# design.net
KiCad netlist of a schematic drawn in EasyEDA Pro
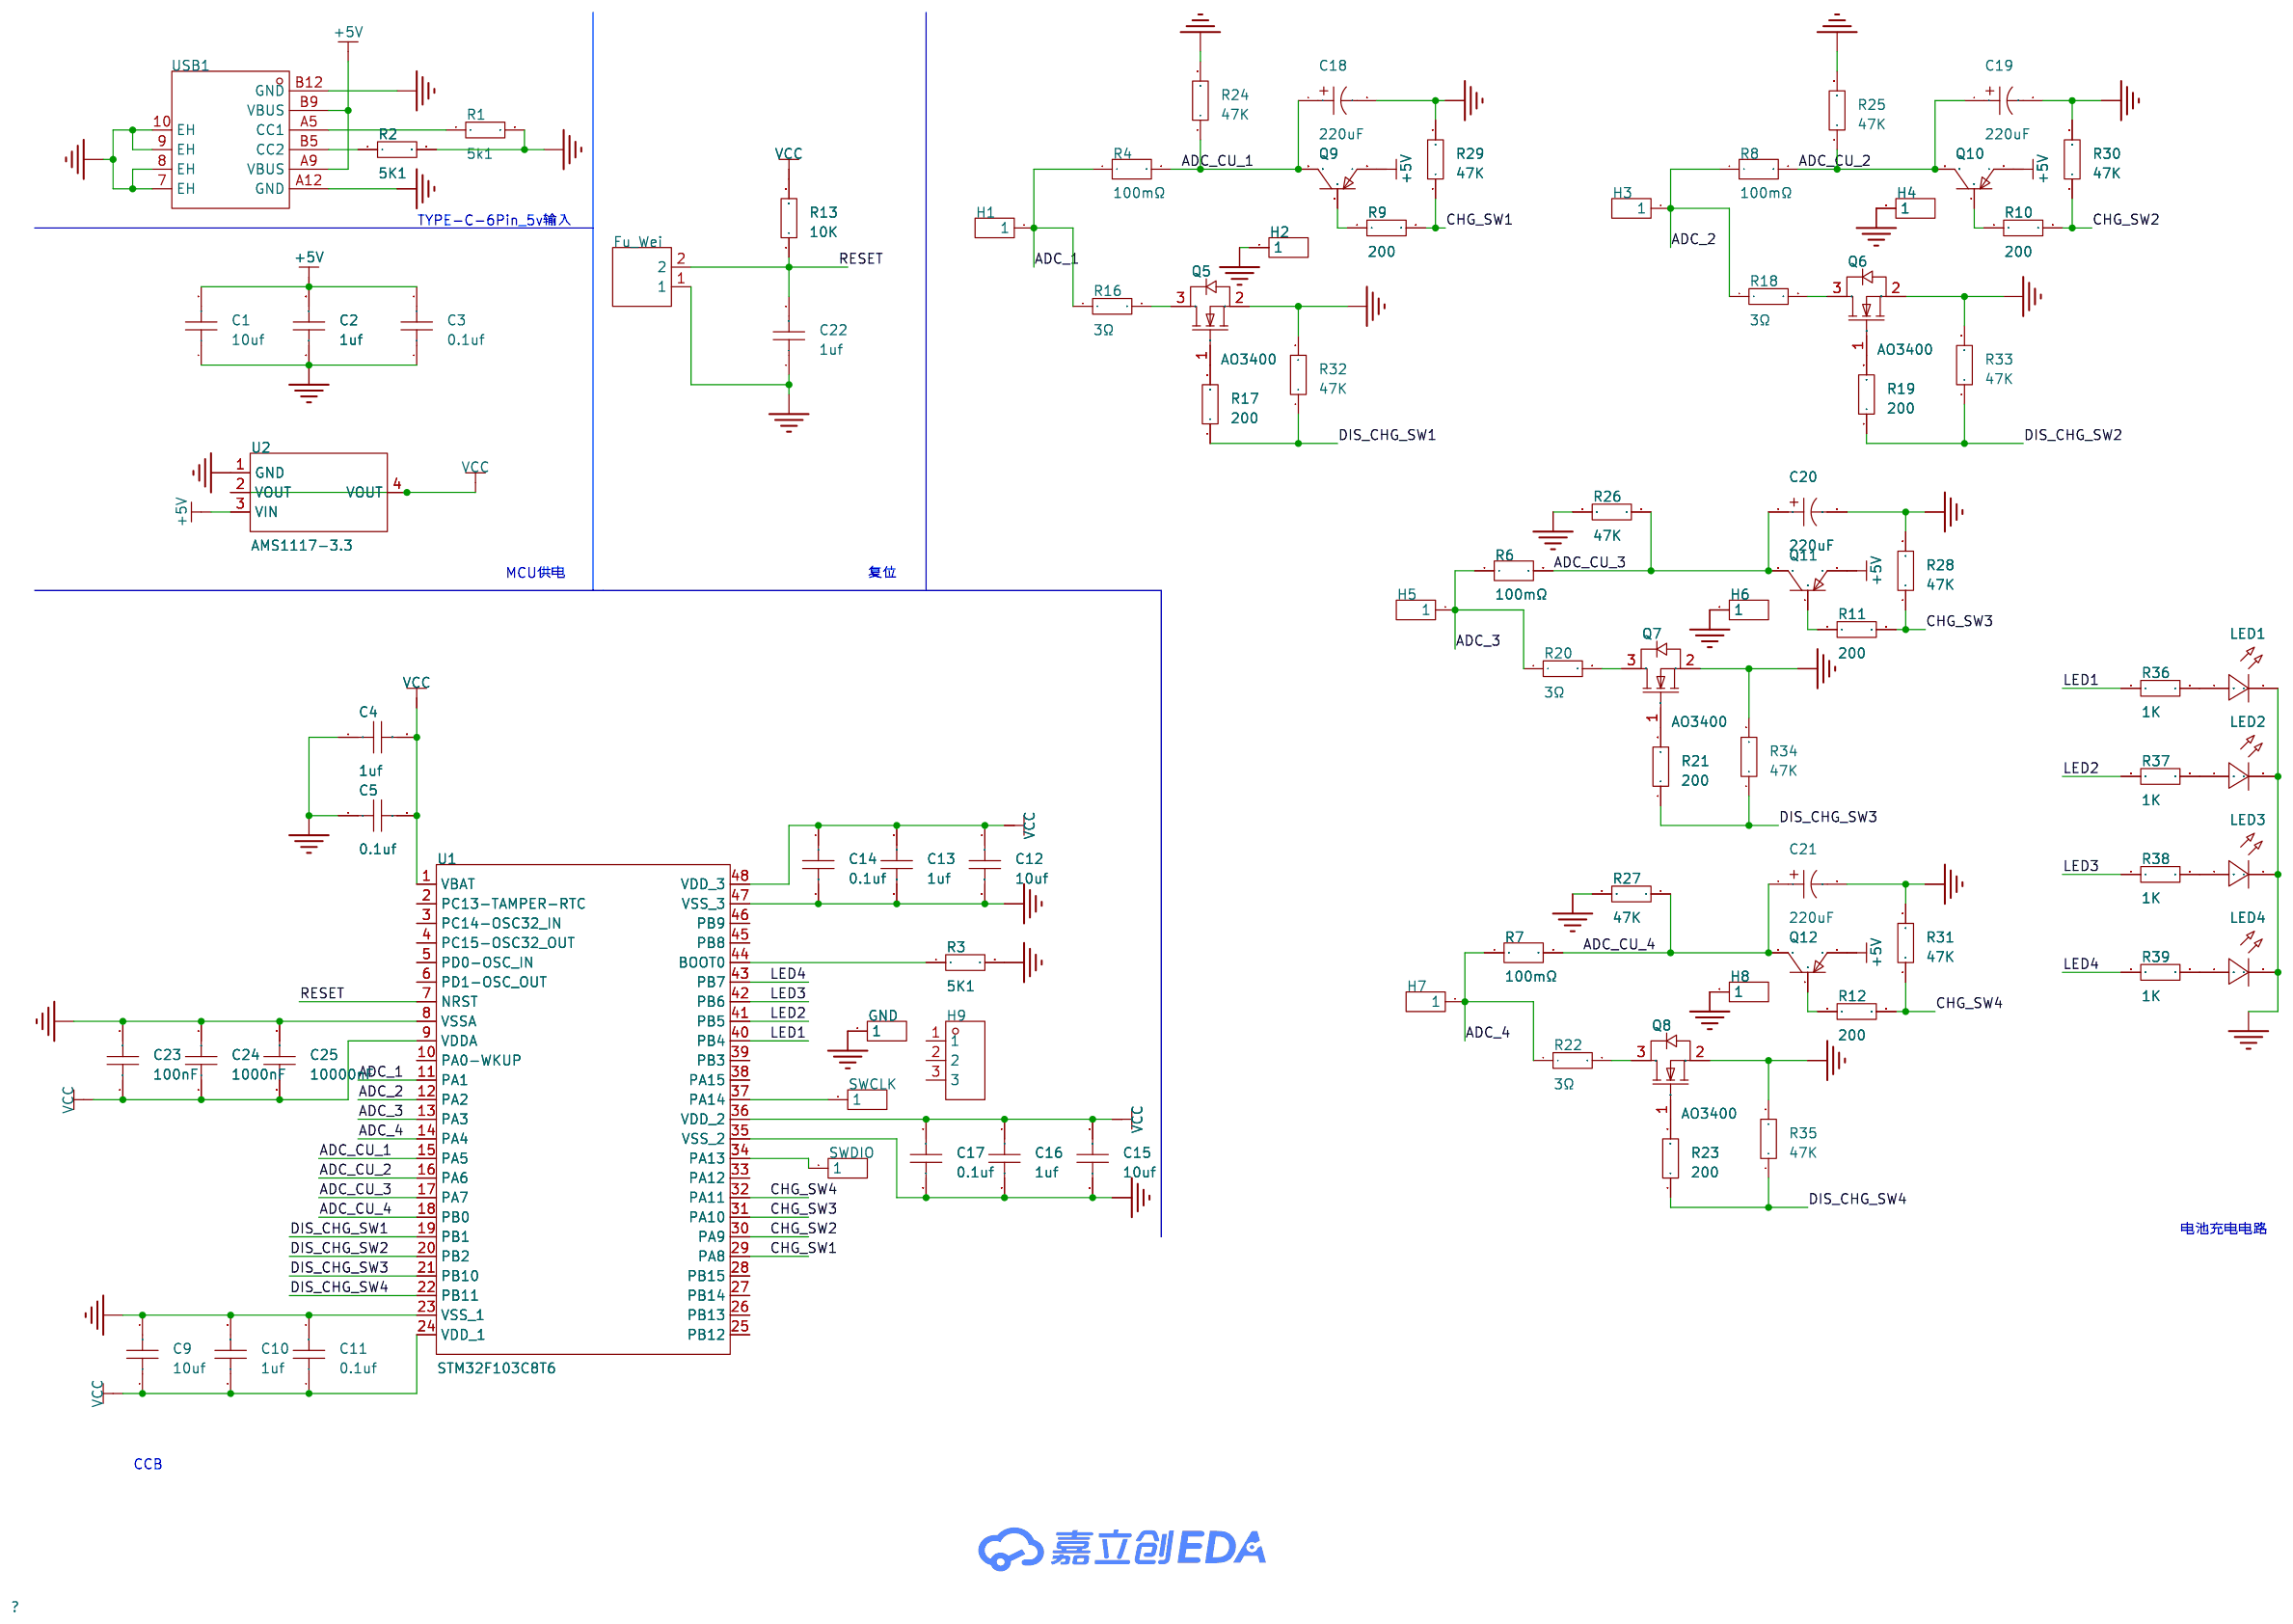
[diagram p0: schematic sheet]

(export (version "E")
  (design (tool "Eeschema 10.0.6"))
  (components
    (comp (ref "C1")
      (value "10uf")
      (footprint "easyedapro:C0603")
      (libsource (lib "easyedapro") (part "Capacitance"))
    )
    (comp (ref "C2")
      (value "1uf")
      (footprint "easyedapro:C0603")
      (libsource (lib "easyedapro") (part "Capacitance"))
    )
    (comp (ref "C3")
      (value "0.1uf")
      (footprint "easyedapro:C0603")
      (libsource (lib "easyedapro") (part "Capacitance"))
    )
    (comp (ref "C4")
      (value "1uf")
      (footprint "easyedapro:C0603")
      (libsource (lib "easyedapro") (part "Capacitance"))
    )
    (comp (ref "C5")
      (value "0.1uf")
      (footprint "easyedapro:C0603")
      (libsource (lib "easyedapro") (part "Capacitance"))
    )
    (comp (ref "C9")
      (value "10uf")
      (footprint "easyedapro:C0603")
      (libsource (lib "easyedapro") (part "Capacitance"))
    )
    (comp (ref "C10")
      (value "1uf")
      (footprint "easyedapro:C0603")
      (libsource (lib "easyedapro") (part "Capacitance"))
    )
    (comp (ref "C11")
      (value "0.1uf")
      (footprint "easyedapro:C0603")
      (libsource (lib "easyedapro") (part "Capacitance"))
    )
    (comp (ref "C12")
      (value "10uf")
      (footprint "easyedapro:C0603")
      (libsource (lib "easyedapro") (part "Capacitance"))
    )
    (comp (ref "C13")
      (value "1uf")
      (footprint "easyedapro:C0603")
      (libsource (lib "easyedapro") (part "Capacitance"))
    )
    (comp (ref "C14")
      (value "0.1uf")
      (footprint "easyedapro:C0603")
      (libsource (lib "easyedapro") (part "Capacitance"))
    )
    (comp (ref "C15")
      (value "10uf")
      (footprint "easyedapro:C0603")
      (libsource (lib "easyedapro") (part "Capacitance"))
    )
    (comp (ref "C16")
      (value "1uf")
      (footprint "easyedapro:C0603")
      (libsource (lib "easyedapro") (part "Capacitance"))
    )
    (comp (ref "C17")
      (value "0.1uf")
      (footprint "easyedapro:C0603")
      (libsource (lib "easyedapro") (part "Capacitance"))
    )
    (comp (ref "C18")
      (value "220uF")
      (footprint "easyedapro:CAP-SMD_L6.0-W3.2")
      (description "容值:220uF;精度:±20%;额定电压:6.3V;等效串联电阻(ESR):45mΩ@100kHz;")
      (fields
        (field (name "Manufacturer Part") "T520C227M006ATE045")
        (field (name "Manufacturer") "KEMET(基美)")
      )
      (libsource (lib "easyedapro") (part "T520C227M006ATE045"))
    )
    (comp (ref "C19")
      (value "220uF")
      (footprint "easyedapro:CAP-SMD_L6.0-W3.2")
      (description "容值:220uF;精度:±20%;额定电压:6.3V;等效串联电阻(ESR):45mΩ@100kHz;")
      (fields
        (field (name "Manufacturer Part") "T520C227M006ATE045")
        (field (name "Manufacturer") "KEMET(基美)")
      )
      (libsource (lib "easyedapro") (part "T520C227M006ATE045"))
    )
    (comp (ref "C20")
      (value "220uF")
      (footprint "easyedapro:CAP-SMD_L6.0-W3.2")
      (description "容值:220uF;精度:±20%;额定电压:6.3V;等效串联电阻(ESR):45mΩ@100kHz;")
      (fields
        (field (name "Manufacturer Part") "T520C227M006ATE045")
        (field (name "Manufacturer") "KEMET(基美)")
      )
      (libsource (lib "easyedapro") (part "T520C227M006ATE045"))
    )
    (comp (ref "C21")
      (value "220uF")
      (footprint "easyedapro:CAP-SMD_L6.0-W3.2")
      (description "容值:220uF;精度:±20%;额定电压:6.3V;等效串联电阻(ESR):45mΩ@100kHz;")
      (fields
        (field (name "Manufacturer Part") "T520C227M006ATE045")
        (field (name "Manufacturer") "KEMET(基美)")
      )
      (libsource (lib "easyedapro") (part "T520C227M006ATE045"))
    )
    (comp (ref "C22")
      (value "1uf")
      (footprint "easyedapro:C0603")
      (libsource (lib "easyedapro") (part "Capacitance"))
    )
    (comp (ref "C23")
      (value "100nF")
      (footprint "easyedapro:C0603")
      (libsource (lib "easyedapro") (part "Capacitance"))
    )
    (comp (ref "C24")
      (value "1000nF")
      (footprint "easyedapro:C0603")
      (libsource (lib "easyedapro") (part "Capacitance"))
    )
    (comp (ref "C25")
      (value "10000nF")
      (footprint "easyedapro:C0603")
      (libsource (lib "easyedapro") (part "Capacitance"))
    )
    (comp (ref "Fu_Wei")
      (value "~")
      (footprint "easyedapro:HDR-TH_2P-P2.54-V-M-1")
      (libsource (lib "easyedapro") (part "210S-1*2P L=11.6MMGold-plated black"))
    )
    (comp (ref "GND")
      (value "~")
      (footprint "easyedapro:HDR-TH_1P-V-M_XKB_X4611WV-01I-C28D40")
      (libsource (lib "easyedapro") (part "HDR_1x1"))
    )
    (comp (ref "H1")
      (value "~")
      (footprint "easyedapro:HDR-TH_1P-V-M_XKB_X4611WV-01I-C28D40")
      (libsource (lib "easyedapro") (part "HDR_1x1"))
    )
    (comp (ref "H2")
      (value "~")
      (footprint "easyedapro:HDR-TH_1P-V-M_XKB_X4611WV-01I-C28D40")
      (libsource (lib "easyedapro") (part "HDR_1x1"))
    )
    (comp (ref "H3")
      (value "~")
      (footprint "easyedapro:HDR-TH_1P-V-M_XKB_X4611WV-01I-C28D40")
      (libsource (lib "easyedapro") (part "HDR_1x1"))
    )
    (comp (ref "H4")
      (value "~")
      (footprint "easyedapro:HDR-TH_1P-V-M_XKB_X4611WV-01I-C28D40")
      (libsource (lib "easyedapro") (part "HDR_1x1"))
    )
    (comp (ref "H5")
      (value "~")
      (footprint "easyedapro:HDR-TH_1P-V-M_XKB_X4611WV-01I-C28D40")
      (libsource (lib "easyedapro") (part "HDR_1x1"))
    )
    (comp (ref "H6")
      (value "~")
      (footprint "easyedapro:HDR-TH_1P-V-M_XKB_X4611WV-01I-C28D40")
      (libsource (lib "easyedapro") (part "HDR_1x1"))
    )
    (comp (ref "H7")
      (value "~")
      (footprint "easyedapro:HDR-TH_1P-V-M_XKB_X4611WV-01I-C28D40")
      (libsource (lib "easyedapro") (part "HDR_1x1"))
    )
    (comp (ref "H8")
      (value "~")
      (footprint "easyedapro:HDR-TH_1P-V-M_XKB_X4611WV-01I-C28D40")
      (libsource (lib "easyedapro") (part "HDR_1x1"))
    )
    (comp (ref "H9")
      (value "~")
      (footprint "easyedapro:HDR-TH_3P-P2.54-V-M")
      (libsource (lib "easyedapro") (part "HDR-M_2.54_1x3P"))
    )
    (comp (ref "LED1")
      (value "~")
      (footprint "easyedapro:LED_TH-3mm")
      (libsource (lib "easyedapro") (part "LED_TH-R"))
    )
    (comp (ref "LED2")
      (value "~")
      (footprint "easyedapro:LED_TH-3mm")
      (libsource (lib "easyedapro") (part "LED_TH-R"))
    )
    (comp (ref "LED3")
      (value "~")
      (footprint "easyedapro:LED_TH-3mm")
      (libsource (lib "easyedapro") (part "LED_TH-R"))
    )
    (comp (ref "LED4")
      (value "~")
      (footprint "easyedapro:LED_TH-3mm")
      (libsource (lib "easyedapro") (part "LED_TH-R"))
    )
    (comp (ref "Q5")
      (value "AO3400")
      (footprint "easyedapro:SOT-23_L2.9-W1.3-P1.90-LS2.4-BR")
      (fields (field (name "Manufacturer") "GOODWORK(固得沃克)"))
      (libsource (lib "easyedapro") (part "AO3400_C2938367"))
    )
    (comp (ref "Q6")
      (value "AO3400")
      (footprint "easyedapro:SOT-23_L2.9-W1.3-P1.90-LS2.4-BR")
      (fields (field (name "Manufacturer") "GOODWORK(固得沃克)"))
      (libsource (lib "easyedapro") (part "AO3400_C2938367"))
    )
    (comp (ref "Q7")
      (value "AO3400")
      (footprint "easyedapro:SOT-23_L2.9-W1.3-P1.90-LS2.4-BR")
      (fields (field (name "Manufacturer") "GOODWORK(固得沃克)"))
      (libsource (lib "easyedapro") (part "AO3400_C2938367"))
    )
    (comp (ref "Q8")
      (value "AO3400")
      (footprint "easyedapro:SOT-23_L2.9-W1.3-P1.90-LS2.4-BR")
      (fields (field (name "Manufacturer") "GOODWORK(固得沃克)"))
      (libsource (lib "easyedapro") (part "AO3400_C2938367"))
    )
    (comp (ref "Q9")
      (value "~")
      (footprint "easyedapro:S8550P_SOT")
      (libsource (lib "easyedapro") (part "PNP"))
    )
    (comp (ref "Q10")
      (value "~")
      (footprint "easyedapro:S8550P_SOT")
      (libsource (lib "easyedapro") (part "PNP"))
    )
    (comp (ref "Q11")
      (value "~")
      (footprint "easyedapro:S8550P_SOT")
      (libsource (lib "easyedapro") (part "PNP"))
    )
    (comp (ref "Q12")
      (value "~")
      (footprint "easyedapro:S8550P_SOT")
      (libsource (lib "easyedapro") (part "PNP"))
    )
    (comp (ref "R1") (value "5k1") (footprint "easyedapro:R0805") (libsource (lib "easyedapro") (part "电阻")))
    (comp (ref "R2") (value "5K1") (footprint "easyedapro:R0805") (libsource (lib "easyedapro") (part "电阻")))
    (comp (ref "R3") (value "5K1") (footprint "easyedapro:R0805") (libsource (lib "easyedapro") (part "电阻")))
    (comp (ref "R4")
      (value "100mΩ")
      (footprint "easyedapro:R2512")
      (description "电阻类型:采样电阻；合金电阻;阻值:100mΩ;精度:±1%;功率:3W;温度系数:±50ppm/°C;")
      (fields (field (name "Manufacturer Part") "RE2512F3R100") (field (name "Manufacturer") "JIERR(捷而瑞)"))
      (libsource (lib "easyedapro") (part "RE2512F3R100"))
    )
    (comp (ref "R6")
      (value "100mΩ")
      (footprint "easyedapro:R2512")
      (description "电阻类型:采样电阻；合金电阻;阻值:100mΩ;精度:±1%;功率:3W;温度系数:±50ppm/°C;")
      (fields (field (name "Manufacturer Part") "RE2512F3R100") (field (name "Manufacturer") "JIERR(捷而瑞)"))
      (libsource (lib "easyedapro") (part "RE2512F3R100"))
    )
    (comp (ref "R7")
      (value "100mΩ")
      (footprint "easyedapro:R2512")
      (description "电阻类型:采样电阻；合金电阻;阻值:100mΩ;精度:±1%;功率:3W;温度系数:±50ppm/°C;")
      (fields (field (name "Manufacturer Part") "RE2512F3R100") (field (name "Manufacturer") "JIERR(捷而瑞)"))
      (libsource (lib "easyedapro") (part "RE2512F3R100"))
    )
    (comp (ref "R8")
      (value "100mΩ")
      (footprint "easyedapro:R2512")
      (description "电阻类型:采样电阻；合金电阻;阻值:100mΩ;精度:±1%;功率:3W;温度系数:±50ppm/°C;")
      (fields (field (name "Manufacturer Part") "RE2512F3R100") (field (name "Manufacturer") "JIERR(捷而瑞)"))
      (libsource (lib "easyedapro") (part "RE2512F3R100"))
    )
    (comp (ref "R9") (value "200") (footprint "easyedapro:R0805") (libsource (lib "easyedapro") (part "电阻")))
    (comp (ref "R10") (value "200") (footprint "easyedapro:R0805") (libsource (lib "easyedapro") (part "电阻")))
    (comp (ref "R11") (value "200") (footprint "easyedapro:R0805") (libsource (lib "easyedapro") (part "电阻")))
    (comp (ref "R12") (value "200") (footprint "easyedapro:R0805") (libsource (lib "easyedapro") (part "电阻")))
    (comp (ref "R13") (value "10K") (footprint "easyedapro:R0805") (libsource (lib "easyedapro") (part "电阻")))
    (comp (ref "R16")
      (value "3Ω")
      (footprint "easyedapro:R2512")
      (description "电阻类型:厚膜电阻;阻值:3Ω;精度:±5%;功率:1W;最大工作电压:200V;温度系数:±200ppm/°C;")
      (fields
        (field (name "Manufacturer Part") "25121WJ030JT4E")
        (field (name "Manufacturer") "UNI-ROYAL(厚声)")
      )
      (libsource (lib "easyedapro") (part "25121WJ030JT4E"))
    )
    (comp (ref "R17") (value "200") (footprint "easyedapro:R0805") (libsource (lib "easyedapro") (part "电阻")))
    (comp (ref "R18")
      (value "3Ω")
      (footprint "easyedapro:R2512")
      (description "电阻类型:厚膜电阻;阻值:3Ω;精度:±5%;功率:1W;最大工作电压:200V;温度系数:±200ppm/°C;")
      (fields
        (field (name "Manufacturer Part") "25121WJ030JT4E")
        (field (name "Manufacturer") "UNI-ROYAL(厚声)")
      )
      (libsource (lib "easyedapro") (part "25121WJ030JT4E"))
    )
    (comp (ref "R19") (value "200") (footprint "easyedapro:R0805") (libsource (lib "easyedapro") (part "电阻")))
    (comp (ref "R20")
      (value "3Ω")
      (footprint "easyedapro:R2512")
      (description "电阻类型:厚膜电阻;阻值:3Ω;精度:±5%;功率:1W;最大工作电压:200V;温度系数:±200ppm/°C;")
      (fields
        (field (name "Manufacturer Part") "25121WJ030JT4E")
        (field (name "Manufacturer") "UNI-ROYAL(厚声)")
      )
      (libsource (lib "easyedapro") (part "25121WJ030JT4E"))
    )
    (comp (ref "R21") (value "200") (footprint "easyedapro:R0805") (libsource (lib "easyedapro") (part "电阻")))
    (comp (ref "R22")
      (value "3Ω")
      (footprint "easyedapro:R2512")
      (description "电阻类型:厚膜电阻;阻值:3Ω;精度:±5%;功率:1W;最大工作电压:200V;温度系数:±200ppm/°C;")
      (fields
        (field (name "Manufacturer Part") "25121WJ030JT4E")
        (field (name "Manufacturer") "UNI-ROYAL(厚声)")
      )
      (libsource (lib "easyedapro") (part "25121WJ030JT4E"))
    )
    (comp (ref "R23") (value "200") (footprint "easyedapro:R0805") (libsource (lib "easyedapro") (part "电阻")))
    (comp (ref "R24") (value "47K") (footprint "easyedapro:R0805") (libsource (lib "easyedapro") (part "电阻")))
    (comp (ref "R25") (value "47K") (footprint "easyedapro:R0805") (libsource (lib "easyedapro") (part "电阻")))
    (comp (ref "R26") (value "47K") (footprint "easyedapro:R0805") (libsource (lib "easyedapro") (part "电阻")))
    (comp (ref "R27") (value "47K") (footprint "easyedapro:R0805") (libsource (lib "easyedapro") (part "电阻")))
    (comp (ref "R28") (value "47K") (footprint "easyedapro:R0805") (libsource (lib "easyedapro") (part "电阻")))
    (comp (ref "R29") (value "47K") (footprint "easyedapro:R0805") (libsource (lib "easyedapro") (part "电阻")))
    (comp (ref "R30") (value "47K") (footprint "easyedapro:R0805") (libsource (lib "easyedapro") (part "电阻")))
    (comp (ref "R31") (value "47K") (footprint "easyedapro:R0805") (libsource (lib "easyedapro") (part "电阻")))
    (comp (ref "R32") (value "47K") (footprint "easyedapro:R0805") (libsource (lib "easyedapro") (part "电阻")))
    (comp (ref "R33") (value "47K") (footprint "easyedapro:R0805") (libsource (lib "easyedapro") (part "电阻")))
    (comp (ref "R34") (value "47K") (footprint "easyedapro:R0805") (libsource (lib "easyedapro") (part "电阻")))
    (comp (ref "R35") (value "47K") (footprint "easyedapro:R0805") (libsource (lib "easyedapro") (part "电阻")))
    (comp (ref "R36") (value "1K") (footprint "easyedapro:R0805") (libsource (lib "easyedapro") (part "电阻")))
    (comp (ref "R37") (value "1K") (footprint "easyedapro:R0805") (libsource (lib "easyedapro") (part "电阻")))
    (comp (ref "R38") (value "1K") (footprint "easyedapro:R0805") (libsource (lib "easyedapro") (part "电阻")))
    (comp (ref "R39") (value "1K") (footprint "easyedapro:R0805") (libsource (lib "easyedapro") (part "电阻")))
    (comp (ref "SWCLK")
      (value "~")
      (footprint "easyedapro:HDR-TH_1P-V-M_XKB_X4611WV-01I-C28D40")
      (libsource (lib "easyedapro") (part "HDR_1x1"))
    )
    (comp (ref "SWDIO")
      (value "~")
      (footprint "easyedapro:HDR-TH_1P-V-M_XKB_X4611WV-01I-C28D40")
      (libsource (lib "easyedapro") (part "HDR_1x1"))
    )
    (comp (ref "U1")
      (value "STM32F103C8T6")
      (footprint "easyedapro:LQFP-48_L7.0-W7.0-P0.50-LS9.0-BL")
      (description "CPU内核:ARM-M3;CPU最大主频:72MHz;应用领域:-;")
      (fields (field (name "Manufacturer") "ST(意法半导体)"))
      (libsource (lib "easyedapro") (part "STM32F103C8T6"))
    )
    (comp (ref "U2")
      (value "AMS1117-3.3")
      (footprint "easyedapro:SOT-223-3_L6.5-W3.4-P2.30-LS7.0-BR")
      (description "输出类型:固定;工作电压:16V;输出电压:3.3V;输出电流:1A;电源纹波抑制比(PSRR):72dB@(120Hz);输出极性:正极;")
      (fields (field (name "Manufacturer") "AMS"))
      (libsource (lib "easyedapro") (part "AMS1117-3.3"))
    )
    (comp (ref "USB1")
      (value "~")
      (footprint "easyedapro:USB_ TYPE-C-6P")
      (libsource (lib "easyedapro") (part "USB_ TYPE-C-6P"))
    )
  )
  (nets
    (net (code "1") (name "+5V") (class "Default")
      (node (ref "C1") (pin "2") (pinfunction "2_2") (pintype "input"))
      (node (ref "C2") (pin "2") (pinfunction "2_2") (pintype "input"))
      (node (ref "C3") (pin "2") (pinfunction "2_2") (pintype "input"))
      (node (ref "Q10") (pin "2") (pinfunction "E_2") (pintype "input"))
      (node (ref "Q11") (pin "2") (pinfunction "E_2") (pintype "input"))
      (node (ref "Q12") (pin "2") (pinfunction "E_2") (pintype "input"))
      (node (ref "Q9") (pin "2") (pinfunction "E_2") (pintype "input"))
      (node (ref "U2") (pin "3") (pinfunction "VIN_3") (pintype "unspecified"))
      (node (ref "USB1") (pin "A9") (pinfunction "VBUS_A9") (pintype "input"))
      (node (ref "USB1") (pin "B9") (pinfunction "VBUS_B9") (pintype "input"))
    )
    (net (code "2") (name "/ADC_1") (class "Default")
      (node (ref "H1") (pin "1") (pinfunction "1_1") (pintype "unspecified"))
      (node (ref "R16") (pin "1") (pinfunction "1_1") (pintype "input"))
      (node (ref "R4") (pin "1") (pinfunction "1_1") (pintype "unspecified"))
      (node (ref "U1") (pin "11") (pinfunction "PA1_11") (pintype "unspecified"))
    )
    (net (code "3") (name "/ADC_2") (class "Default")
      (node (ref "H3") (pin "1") (pinfunction "1_1") (pintype "unspecified"))
      (node (ref "R18") (pin "1") (pinfunction "1_1") (pintype "input"))
      (node (ref "R8") (pin "1") (pinfunction "1_1") (pintype "unspecified"))
      (node (ref "U1") (pin "12") (pinfunction "PA2_12") (pintype "unspecified"))
    )
    (net (code "4") (name "/ADC_3") (class "Default")
      (node (ref "H5") (pin "1") (pinfunction "1_1") (pintype "unspecified"))
      (node (ref "R20") (pin "1") (pinfunction "1_1") (pintype "input"))
      (node (ref "R6") (pin "1") (pinfunction "1_1") (pintype "unspecified"))
      (node (ref "U1") (pin "13") (pinfunction "PA3_13") (pintype "unspecified"))
    )
    (net (code "5") (name "/ADC_4") (class "Default")
      (node (ref "H7") (pin "1") (pinfunction "1_1") (pintype "unspecified"))
      (node (ref "R22") (pin "1") (pinfunction "1_1") (pintype "input"))
      (node (ref "R7") (pin "1") (pinfunction "1_1") (pintype "unspecified"))
      (node (ref "U1") (pin "14") (pinfunction "PA4_14") (pintype "unspecified"))
    )
    (net (code "6") (name "/ADC_CU_1") (class "Default")
      (node (ref "C18") (pin "1") (pinfunction "1_1") (pintype "input"))
      (node (ref "Q9") (pin "3") (pinfunction "C_3") (pintype "input"))
      (node (ref "R24") (pin "1") (pinfunction "1_1") (pintype "input"))
      (node (ref "R4") (pin "2") (pinfunction "2_2") (pintype "unspecified"))
      (node (ref "U1") (pin "15") (pinfunction "PA5_15") (pintype "unspecified"))
    )
    (net (code "7") (name "/ADC_CU_2") (class "Default")
      (node (ref "C19") (pin "1") (pinfunction "1_1") (pintype "input"))
      (node (ref "Q10") (pin "3") (pinfunction "C_3") (pintype "input"))
      (node (ref "R25") (pin "1") (pinfunction "1_1") (pintype "input"))
      (node (ref "R8") (pin "2") (pinfunction "2_2") (pintype "unspecified"))
      (node (ref "U1") (pin "16") (pinfunction "PA6_16") (pintype "unspecified"))
    )
    (net (code "8") (name "/ADC_CU_3") (class "Default")
      (node (ref "C20") (pin "1") (pinfunction "1_1") (pintype "input"))
      (node (ref "Q11") (pin "3") (pinfunction "C_3") (pintype "input"))
      (node (ref "R26") (pin "1") (pinfunction "1_1") (pintype "input"))
      (node (ref "R6") (pin "2") (pinfunction "2_2") (pintype "unspecified"))
      (node (ref "U1") (pin "17") (pinfunction "PA7_17") (pintype "unspecified"))
    )
    (net (code "9") (name "/ADC_CU_4") (class "Default")
      (node (ref "C21") (pin "1") (pinfunction "1_1") (pintype "input"))
      (node (ref "Q12") (pin "3") (pinfunction "C_3") (pintype "input"))
      (node (ref "R27") (pin "1") (pinfunction "1_1") (pintype "input"))
      (node (ref "R7") (pin "2") (pinfunction "2_2") (pintype "unspecified"))
      (node (ref "U1") (pin "18") (pinfunction "PB0_18") (pintype "unspecified"))
    )
    (net (code "10") (name "/CHG_SW1") (class "Default")
      (node (ref "R29") (pin "1") (pinfunction "1_1") (pintype "input"))
      (node (ref "R9") (pin "2") (pinfunction "2_2") (pintype "input"))
      (node (ref "U1") (pin "29") (pinfunction "PA8_29") (pintype "unspecified"))
    )
    (net (code "11") (name "/CHG_SW2") (class "Default")
      (node (ref "R10") (pin "2") (pinfunction "2_2") (pintype "input"))
      (node (ref "R30") (pin "1") (pinfunction "1_1") (pintype "input"))
      (node (ref "U1") (pin "30") (pinfunction "PA9_30") (pintype "unspecified"))
    )
    (net (code "12") (name "/CHG_SW3") (class "Default")
      (node (ref "R11") (pin "2") (pinfunction "2_2") (pintype "input"))
      (node (ref "R28") (pin "1") (pinfunction "1_1") (pintype "input"))
      (node (ref "U1") (pin "31") (pinfunction "PA10_31") (pintype "unspecified"))
    )
    (net (code "13") (name "/CHG_SW4") (class "Default")
      (node (ref "R12") (pin "2") (pinfunction "2_2") (pintype "input"))
      (node (ref "R31") (pin "1") (pinfunction "1_1") (pintype "input"))
      (node (ref "U1") (pin "32") (pinfunction "PA11_32") (pintype "unspecified"))
    )
    (net (code "14") (name "/DIS_CHG_SW1") (class "Default")
      (node (ref "R17") (pin "1") (pinfunction "1_1") (pintype "input"))
      (node (ref "R32") (pin "1") (pinfunction "1_1") (pintype "input"))
      (node (ref "U1") (pin "19") (pinfunction "PB1_19") (pintype "unspecified"))
    )
    (net (code "15") (name "/DIS_CHG_SW2") (class "Default")
      (node (ref "R19") (pin "1") (pinfunction "1_1") (pintype "input"))
      (node (ref "R33") (pin "1") (pinfunction "1_1") (pintype "input"))
      (node (ref "U1") (pin "20") (pinfunction "PB2_20") (pintype "unspecified"))
    )
    (net (code "16") (name "/DIS_CHG_SW3") (class "Default")
      (node (ref "R21") (pin "1") (pinfunction "1_1") (pintype "input"))
      (node (ref "R34") (pin "1") (pinfunction "1_1") (pintype "input"))
      (node (ref "U1") (pin "21") (pinfunction "PB10_21") (pintype "unspecified"))
    )
    (net (code "17") (name "/DIS_CHG_SW4") (class "Default")
      (node (ref "R23") (pin "1") (pinfunction "1_1") (pintype "input"))
      (node (ref "R35") (pin "1") (pinfunction "1_1") (pintype "input"))
      (node (ref "U1") (pin "22") (pinfunction "PB11_22") (pintype "unspecified"))
    )
    (net (code "18") (name "/LED1") (class "Default")
      (node (ref "R36") (pin "1") (pinfunction "1_1") (pintype "input"))
      (node (ref "U1") (pin "40") (pinfunction "PB4_40") (pintype "unspecified"))
    )
    (net (code "19") (name "/LED2") (class "Default")
      (node (ref "R37") (pin "1") (pinfunction "1_1") (pintype "input"))
      (node (ref "U1") (pin "41") (pinfunction "PB5_41") (pintype "unspecified"))
    )
    (net (code "20") (name "/LED3") (class "Default")
      (node (ref "R38") (pin "1") (pinfunction "1_1") (pintype "input"))
      (node (ref "U1") (pin "42") (pinfunction "PB6_42") (pintype "unspecified"))
    )
    (net (code "21") (name "/LED4") (class "Default")
      (node (ref "R39") (pin "1") (pinfunction "1_1") (pintype "input"))
      (node (ref "U1") (pin "43") (pinfunction "PB7_43") (pintype "unspecified"))
    )
    (net (code "22") (name "/RESET") (class "Default")
      (node (ref "C22") (pin "2") (pinfunction "2_2") (pintype "input"))
      (node (ref "Fu_Wei") (pin "2") (pinfunction "2_2") (pintype "unspecified"))
      (node (ref "R13") (pin "1") (pinfunction "1_1") (pintype "input"))
      (node (ref "U1") (pin "7") (pinfunction "NRST_7") (pintype "unspecified"))
    )
    (net (code "23") (name "GND") (class "Default")
      (node (ref "C1") (pin "1") (pinfunction "1_1") (pintype "input"))
      (node (ref "C10") (pin "2") (pinfunction "2_2") (pintype "input"))
      (node (ref "C11") (pin "2") (pinfunction "2_2") (pintype "input"))
      (node (ref "C12") (pin "2") (pinfunction "2_2") (pintype "input"))
      (node (ref "C13") (pin "2") (pinfunction "2_2") (pintype "input"))
      (node (ref "C14") (pin "2") (pinfunction "2_2") (pintype "input"))
      (node (ref "C15") (pin "2") (pinfunction "2_2") (pintype "input"))
      (node (ref "C16") (pin "2") (pinfunction "2_2") (pintype "input"))
      (node (ref "C17") (pin "2") (pinfunction "2_2") (pintype "input"))
      (node (ref "C18") (pin "2") (pinfunction "2_2") (pintype "input"))
      (node (ref "C19") (pin "2") (pinfunction "2_2") (pintype "input"))
      (node (ref "C2") (pin "1") (pinfunction "1_1") (pintype "input"))
      (node (ref "C20") (pin "2") (pinfunction "2_2") (pintype "input"))
      (node (ref "C21") (pin "2") (pinfunction "2_2") (pintype "input"))
      (node (ref "C22") (pin "1") (pinfunction "1_1") (pintype "input"))
      (node (ref "C23") (pin "2") (pinfunction "2_2") (pintype "input"))
      (node (ref "C24") (pin "2") (pinfunction "2_2") (pintype "input"))
      (node (ref "C25") (pin "2") (pinfunction "2_2") (pintype "input"))
      (node (ref "C3") (pin "1") (pinfunction "1_1") (pintype "input"))
      (node (ref "C4") (pin "1") (pinfunction "1_1") (pintype "input"))
      (node (ref "C5") (pin "1") (pinfunction "1_1") (pintype "input"))
      (node (ref "C9") (pin "2") (pinfunction "2_2") (pintype "input"))
      (node (ref "Fu_Wei") (pin "1") (pinfunction "1_1") (pintype "unspecified"))
      (node (ref "GND") (pin "1") (pinfunction "1_1") (pintype "unspecified"))
      (node (ref "H2") (pin "1") (pinfunction "1_1") (pintype "unspecified"))
      (node (ref "H4") (pin "1") (pinfunction "1_1") (pintype "unspecified"))
      (node (ref "H6") (pin "1") (pinfunction "1_1") (pintype "unspecified"))
      (node (ref "H8") (pin "1") (pinfunction "1_1") (pintype "unspecified"))
      (node (ref "LED1") (pin "2") (pinfunction "A_2") (pintype "input"))
      (node (ref "LED2") (pin "2") (pinfunction "A_2") (pintype "input"))
      (node (ref "LED3") (pin "2") (pinfunction "A_2") (pintype "input"))
      (node (ref "LED4") (pin "2") (pinfunction "A_2") (pintype "input"))
      (node (ref "Q5") (pin "2") (pinfunction "S_2") (pintype "unspecified"))
      (node (ref "Q6") (pin "2") (pinfunction "S_2") (pintype "unspecified"))
      (node (ref "Q7") (pin "2") (pinfunction "S_2") (pintype "unspecified"))
      (node (ref "Q8") (pin "2") (pinfunction "S_2") (pintype "unspecified"))
      (node (ref "R1") (pin "2") (pinfunction "2_2") (pintype "input"))
      (node (ref "R2") (pin "2") (pinfunction "2_2") (pintype "input"))
      (node (ref "R24") (pin "2") (pinfunction "2_2") (pintype "input"))
      (node (ref "R25") (pin "2") (pinfunction "2_2") (pintype "input"))
      (node (ref "R26") (pin "2") (pinfunction "2_2") (pintype "input"))
      (node (ref "R27") (pin "2") (pinfunction "2_2") (pintype "input"))
      (node (ref "R28") (pin "2") (pinfunction "2_2") (pintype "input"))
      (node (ref "R29") (pin "2") (pinfunction "2_2") (pintype "input"))
      (node (ref "R3") (pin "2") (pinfunction "2_2") (pintype "input"))
      (node (ref "R30") (pin "2") (pinfunction "2_2") (pintype "input"))
      (node (ref "R31") (pin "2") (pinfunction "2_2") (pintype "input"))
      (node (ref "R32") (pin "2") (pinfunction "2_2") (pintype "input"))
      (node (ref "R33") (pin "2") (pinfunction "2_2") (pintype "input"))
      (node (ref "R34") (pin "2") (pinfunction "2_2") (pintype "input"))
      (node (ref "R35") (pin "2") (pinfunction "2_2") (pintype "input"))
      (node (ref "U1") (pin "23") (pinfunction "VSS_1_23") (pintype "unspecified"))
      (node (ref "U1") (pin "35") (pinfunction "VSS_2_35") (pintype "unspecified"))
      (node (ref "U1") (pin "47") (pinfunction "VSS_3_47") (pintype "unspecified"))
      (node (ref "U1") (pin "8") (pinfunction "VSSA_8") (pintype "unspecified"))
      (node (ref "U2") (pin "1") (pinfunction "GND_1") (pintype "unspecified"))
      (node (ref "USB1") (pin "10") (pinfunction "EH_10") (pintype "input"))
      (node (ref "USB1") (pin "7") (pinfunction "EH_7") (pintype "input"))
      (node (ref "USB1") (pin "8") (pinfunction "EH_8") (pintype "input"))
      (node (ref "USB1") (pin "9") (pinfunction "EH_9") (pintype "input"))
      (node (ref "USB1") (pin "A12") (pinfunction "GND_A12") (pintype "input"))
      (node (ref "USB1") (pin "B12") (pinfunction "GND_B12") (pintype "input"))
    )
    (net (code "24") (name "Net-(LED1-C)") (class "Default")
      (node (ref "LED1") (pin "1") (pinfunction "C_1") (pintype "input"))
      (node (ref "R36") (pin "2") (pinfunction "2_2") (pintype "input"))
    )
    (net (code "25") (name "Net-(LED2-C)") (class "Default")
      (node (ref "LED2") (pin "1") (pinfunction "C_1") (pintype "input"))
      (node (ref "R37") (pin "2") (pinfunction "2_2") (pintype "input"))
    )
    (net (code "26") (name "Net-(LED3-C)") (class "Default")
      (node (ref "LED3") (pin "1") (pinfunction "C_1") (pintype "input"))
      (node (ref "R38") (pin "2") (pinfunction "2_2") (pintype "input"))
    )
    (net (code "27") (name "Net-(LED4-C)") (class "Default")
      (node (ref "LED4") (pin "1") (pinfunction "C_1") (pintype "input"))
      (node (ref "R39") (pin "2") (pinfunction "2_2") (pintype "input"))
    )
    (net (code "28") (name "Net-(Q5-D)") (class "Default")
      (node (ref "Q5") (pin "3") (pinfunction "D_3") (pintype "unspecified"))
      (node (ref "R16") (pin "2") (pinfunction "2_2") (pintype "input"))
    )
    (net (code "29") (name "Net-(Q5-G)") (class "Default")
      (node (ref "Q5") (pin "1") (pinfunction "G_1") (pintype "unspecified"))
      (node (ref "R17") (pin "2") (pinfunction "2_2") (pintype "input"))
    )
    (net (code "30") (name "Net-(Q6-D)") (class "Default")
      (node (ref "Q6") (pin "3") (pinfunction "D_3") (pintype "unspecified"))
      (node (ref "R18") (pin "2") (pinfunction "2_2") (pintype "input"))
    )
    (net (code "31") (name "Net-(Q6-G)") (class "Default")
      (node (ref "Q6") (pin "1") (pinfunction "G_1") (pintype "unspecified"))
      (node (ref "R19") (pin "2") (pinfunction "2_2") (pintype "input"))
    )
    (net (code "32") (name "Net-(Q7-D)") (class "Default")
      (node (ref "Q7") (pin "3") (pinfunction "D_3") (pintype "unspecified"))
      (node (ref "R20") (pin "2") (pinfunction "2_2") (pintype "input"))
    )
    (net (code "33") (name "Net-(Q7-G)") (class "Default")
      (node (ref "Q7") (pin "1") (pinfunction "G_1") (pintype "unspecified"))
      (node (ref "R21") (pin "2") (pinfunction "2_2") (pintype "input"))
    )
    (net (code "34") (name "Net-(Q8-D)") (class "Default")
      (node (ref "Q8") (pin "3") (pinfunction "D_3") (pintype "unspecified"))
      (node (ref "R22") (pin "2") (pinfunction "2_2") (pintype "input"))
    )
    (net (code "35") (name "Net-(Q8-G)") (class "Default")
      (node (ref "Q8") (pin "1") (pinfunction "G_1") (pintype "unspecified"))
      (node (ref "R23") (pin "2") (pinfunction "2_2") (pintype "input"))
    )
    (net (code "36") (name "Net-(Q9-B)") (class "Default")
      (node (ref "Q9") (pin "1") (pinfunction "B_1") (pintype "input"))
      (node (ref "R9") (pin "1") (pinfunction "1_1") (pintype "input"))
    )
    (net (code "37") (name "Net-(Q10-B)") (class "Default")
      (node (ref "Q10") (pin "1") (pinfunction "B_1") (pintype "input"))
      (node (ref "R10") (pin "1") (pinfunction "1_1") (pintype "input"))
    )
    (net (code "38") (name "Net-(Q11-B)") (class "Default")
      (node (ref "Q11") (pin "1") (pinfunction "B_1") (pintype "input"))
      (node (ref "R11") (pin "1") (pinfunction "1_1") (pintype "input"))
    )
    (net (code "39") (name "Net-(Q12-B)") (class "Default")
      (node (ref "Q12") (pin "1") (pinfunction "B_1") (pintype "input"))
      (node (ref "R12") (pin "1") (pinfunction "1_1") (pintype "input"))
    )
    (net (code "40") (name "Net-(U1-BOOT0)") (class "Default")
      (node (ref "R3") (pin "1") (pinfunction "1_1") (pintype "input"))
      (node (ref "U1") (pin "44") (pinfunction "BOOT0_44") (pintype "unspecified"))
    )
    (net (code "41") (name "Net-(U1-PA13)") (class "Default")
      (node (ref "SWDIO") (pin "1") (pinfunction "1_1") (pintype "unspecified"))
      (node (ref "U1") (pin "34") (pinfunction "PA13_34") (pintype "unspecified"))
    )
    (net (code "42") (name "Net-(U1-PA14)") (class "Default")
      (node (ref "SWCLK") (pin "1") (pinfunction "1_1") (pintype "unspecified"))
      (node (ref "U1") (pin "37") (pinfunction "PA14_37") (pintype "unspecified"))
    )
    (net (code "43") (name "Net-(USB1-CC1)") (class "Default")
      (node (ref "R1") (pin "1") (pinfunction "1_1") (pintype "input"))
      (node (ref "USB1") (pin "A5") (pinfunction "CC1_A5") (pintype "input"))
    )
    (net (code "44") (name "Net-(USB1-CC2)") (class "Default")
      (node (ref "R2") (pin "1") (pinfunction "1_1") (pintype "input"))
      (node (ref "USB1") (pin "B5") (pinfunction "CC2_B5") (pintype "input"))
    )
    (net (code "45") (name "VCC") (class "Default")
      (node (ref "C10") (pin "1") (pinfunction "1_1") (pintype "input"))
      (node (ref "C11") (pin "1") (pinfunction "1_1") (pintype "input"))
      (node (ref "C12") (pin "1") (pinfunction "1_1") (pintype "input"))
      (node (ref "C13") (pin "1") (pinfunction "1_1") (pintype "input"))
      (node (ref "C14") (pin "1") (pinfunction "1_1") (pintype "input"))
      (node (ref "C15") (pin "1") (pinfunction "1_1") (pintype "input"))
      (node (ref "C16") (pin "1") (pinfunction "1_1") (pintype "input"))
      (node (ref "C17") (pin "1") (pinfunction "1_1") (pintype "input"))
      (node (ref "C23") (pin "1") (pinfunction "1_1") (pintype "input"))
      (node (ref "C24") (pin "1") (pinfunction "1_1") (pintype "input"))
      (node (ref "C25") (pin "1") (pinfunction "1_1") (pintype "input"))
      (node (ref "C4") (pin "2") (pinfunction "2_2") (pintype "input"))
      (node (ref "C5") (pin "2") (pinfunction "2_2") (pintype "input"))
      (node (ref "C9") (pin "1") (pinfunction "1_1") (pintype "input"))
      (node (ref "R13") (pin "2") (pinfunction "2_2") (pintype "input"))
      (node (ref "U1") (pin "1") (pinfunction "VBAT_1") (pintype "unspecified"))
      (node (ref "U1") (pin "24") (pinfunction "VDD_1_24") (pintype "unspecified"))
      (node (ref "U1") (pin "36") (pinfunction "VDD_2_36") (pintype "unspecified"))
      (node (ref "U1") (pin "48") (pinfunction "VDD_3_48") (pintype "unspecified"))
      (node (ref "U1") (pin "9") (pinfunction "VDDA_9") (pintype "unspecified"))
      (node (ref "U2") (pin "2") (pinfunction "VOUT_2") (pintype "unspecified"))
      (node (ref "U2") (pin "4") (pinfunction "VOUT_4") (pintype "unspecified"))
    )
    (net (code "46") (name "unconnected-(H9-Pad1)") (class "Default")
      (node (ref "H9") (pin "1") (pinfunction "1_1") (pintype "input"))
    )
    (net (code "47") (name "unconnected-(H9-Pad2)") (class "Default")
      (node (ref "H9") (pin "2") (pinfunction "2_2") (pintype "input"))
    )
    (net (code "48") (name "unconnected-(H9-Pad3)") (class "Default")
      (node (ref "H9") (pin "3") (pinfunction "3_3") (pintype "input"))
    )
    (net (code "49") (name "unconnected-(U1-PA0-WKUP-Pad10)") (class "Default")
      (node (ref "U1") (pin "10") (pinfunction "PA0-WKUP_10") (pintype "unspecified"))
    )
    (net (code "50") (name "unconnected-(U1-PA12-Pad33)") (class "Default")
      (node (ref "U1") (pin "33") (pinfunction "PA12_33") (pintype "unspecified"))
    )
    (net (code "51") (name "unconnected-(U1-PA15-Pad38)") (class "Default")
      (node (ref "U1") (pin "38") (pinfunction "PA15_38") (pintype "unspecified"))
    )
    (net (code "52") (name "unconnected-(U1-PB3-Pad39)") (class "Default")
      (node (ref "U1") (pin "39") (pinfunction "PB3_39") (pintype "unspecified"))
    )
    (net (code "53") (name "unconnected-(U1-PB8-Pad45)") (class "Default")
      (node (ref "U1") (pin "45") (pinfunction "PB8_45") (pintype "unspecified"))
    )
    (net (code "54") (name "unconnected-(U1-PB9-Pad46)") (class "Default")
      (node (ref "U1") (pin "46") (pinfunction "PB9_46") (pintype "unspecified"))
    )
    (net (code "55") (name "unconnected-(U1-PB12-Pad25)") (class "Default")
      (node (ref "U1") (pin "25") (pinfunction "PB12_25") (pintype "unspecified"))
    )
    (net (code "56") (name "unconnected-(U1-PB13-Pad26)") (class "Default")
      (node (ref "U1") (pin "26") (pinfunction "PB13_26") (pintype "unspecified"))
    )
    (net (code "57") (name "unconnected-(U1-PB14-Pad27)") (class "Default")
      (node (ref "U1") (pin "27") (pinfunction "PB14_27") (pintype "unspecified"))
    )
    (net (code "58") (name "unconnected-(U1-PB15-Pad28)") (class "Default")
      (node (ref "U1") (pin "28") (pinfunction "PB15_28") (pintype "unspecified"))
    )
    (net (code "59") (name "unconnected-(U1-PC13-TAMPER-RTC-Pad2)") (class "Default")
      (node (ref "U1") (pin "2") (pinfunction "PC13-TAMPER-RTC_2") (pintype "unspecified"))
    )
    (net (code "60") (name "unconnected-(U1-PC14-OSC32_IN-Pad3)") (class "Default")
      (node (ref "U1") (pin "3") (pinfunction "PC14-OSC32_IN_3") (pintype "unspecified"))
    )
    (net (code "61") (name "unconnected-(U1-PC15-OSC32_OUT-Pad4)") (class "Default")
      (node (ref "U1") (pin "4") (pinfunction "PC15-OSC32_OUT_4") (pintype "unspecified"))
    )
    (net (code "62") (name "unconnected-(U1-PD0-OSC_IN-Pad5)") (class "Default")
      (node (ref "U1") (pin "5") (pinfunction "PD0-OSC_IN_5") (pintype "unspecified"))
    )
    (net (code "63") (name "unconnected-(U1-PD1-OSC_OUT-Pad6)") (class "Default")
      (node (ref "U1") (pin "6") (pinfunction "PD1-OSC_OUT_6") (pintype "unspecified"))
    )
  )
)
